# ArithSlice.net
KiCad netlist of a schematic drawn in EAGLE
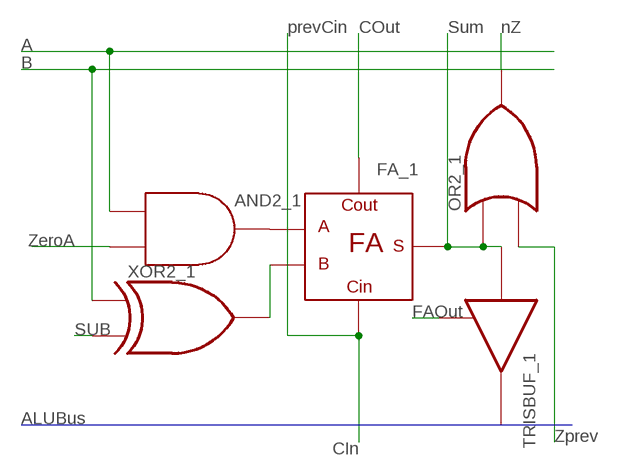
[diagram p0: schematic, sheet 1]

(export (version "E")
  (design (tool "Eeschema 10.0.6"))
  (components
    (comp (ref "AND2_1")
      (value "AND2")
      (footprint "eagle-import:3PIN")
      (libsource (lib "eagle-import") (part "AND2"))
    )
    (comp (ref "FA_1")
      (value "FULLADDER")
      (footprint "eagle-import:5PIN")
      (libsource (lib "eagle-import") (part "FULLADDER"))
    )
    (comp (ref "OR2_1")
      (value "OR2")
      (footprint "eagle-import:3PIN")
      (libsource (lib "eagle-import") (part "OR2"))
    )
    (comp (ref "TRISBUF_1")
      (value "TRISBUF")
      (footprint "eagle-import:3PIN")
      (libsource (lib "eagle-import") (part "TRISBUF"))
    )
    (comp (ref "XOR2_1")
      (value "XOR2")
      (footprint "eagle-import:3PIN")
      (libsource (lib "eagle-import") (part "XOR2"))
    )
  )
  (nets
    (net (code "1") (name "Net-(AND2_1-O)") (class "Default")
      (node (ref "AND2_1") (pin "P$3") (pinfunction "O_P$3") (pintype "output"))
      (node (ref "FA_1") (pin "P$1") (pinfunction "A_P$1") (pintype "bidirectional"))
    )
    (net (code "2") (name "Net-(FA_1-B)") (class "Default")
      (node (ref "FA_1") (pin "P$2") (pinfunction "B_P$2") (pintype "bidirectional"))
      (node (ref "XOR2_1") (pin "P$3") (pinfunction "O_P$3") (pintype "output"))
    )
    (net (code "3") (name "Net-(FA_1-S)") (class "Default")
      (node (ref "FA_1") (pin "P$5") (pinfunction "S_P$5") (pintype "bidirectional"))
      (node (ref "OR2_1") (pin "P$1") (pinfunction "I0_P$1") (pintype "input"))
      (node (ref "TRISBUF_1") (pin "P$1") (pinfunction "I_P$1") (pintype "input"))
    )
    (net (code "4") (name "unconnected-(AND2_1-A-PadP$1)") (class "Default")
      (node (ref "AND2_1") (pin "P$1") (pinfunction "A_P$1") (pintype "input"))
    )
    (net (code "5") (name "unconnected-(AND2_1-I1-PadP$2)") (class "Default")
      (node (ref "AND2_1") (pin "P$2") (pinfunction "I1_P$2") (pintype "input"))
    )
    (net (code "6") (name "unconnected-(FA_1-CIN-PadP$3)") (class "Default")
      (node (ref "FA_1") (pin "P$3") (pinfunction "CIN_P$3") (pintype "bidirectional"))
    )
    (net (code "7") (name "unconnected-(FA_1-COUT-PadP$4)") (class "Default")
      (node (ref "FA_1") (pin "P$4") (pinfunction "COUT_P$4") (pintype "bidirectional"))
    )
    (net (code "8") (name "unconnected-(OR2_1-I1-PadP$2)") (class "Default")
      (node (ref "OR2_1") (pin "P$2") (pinfunction "I1_P$2") (pintype "input"))
    )
    (net (code "9") (name "unconnected-(OR2_1-O-PadP$3)") (class "Default")
      (node (ref "OR2_1") (pin "P$3") (pinfunction "O_P$3") (pintype "output"))
    )
    (net (code "10") (name "unconnected-(TRISBUF_1-O-PadP$2)") (class "Default")
      (node (ref "TRISBUF_1") (pin "P$2") (pinfunction "O_P$2") (pintype "open_collector"))
    )
    (net (code "11") (name "unconnected-(TRISBUF_1-P$1-PadP$3)") (class "Default")
      (node (ref "TRISBUF_1") (pin "P$3") (pinfunction "P$1_P$3") (pintype "bidirectional"))
    )
    (net (code "12") (name "unconnected-(XOR2_1-I0-PadP$1)") (class "Default")
      (node (ref "XOR2_1") (pin "P$1") (pinfunction "I0_P$1") (pintype "input"))
    )
    (net (code "13") (name "unconnected-(XOR2_1-I1-PadP$2)") (class "Default")
      (node (ref "XOR2_1") (pin "P$2") (pinfunction "I1_P$2") (pintype "input"))
    )
  )
)
